# Power.net
KiCad netlist of a schematic drawn in Altium Designer
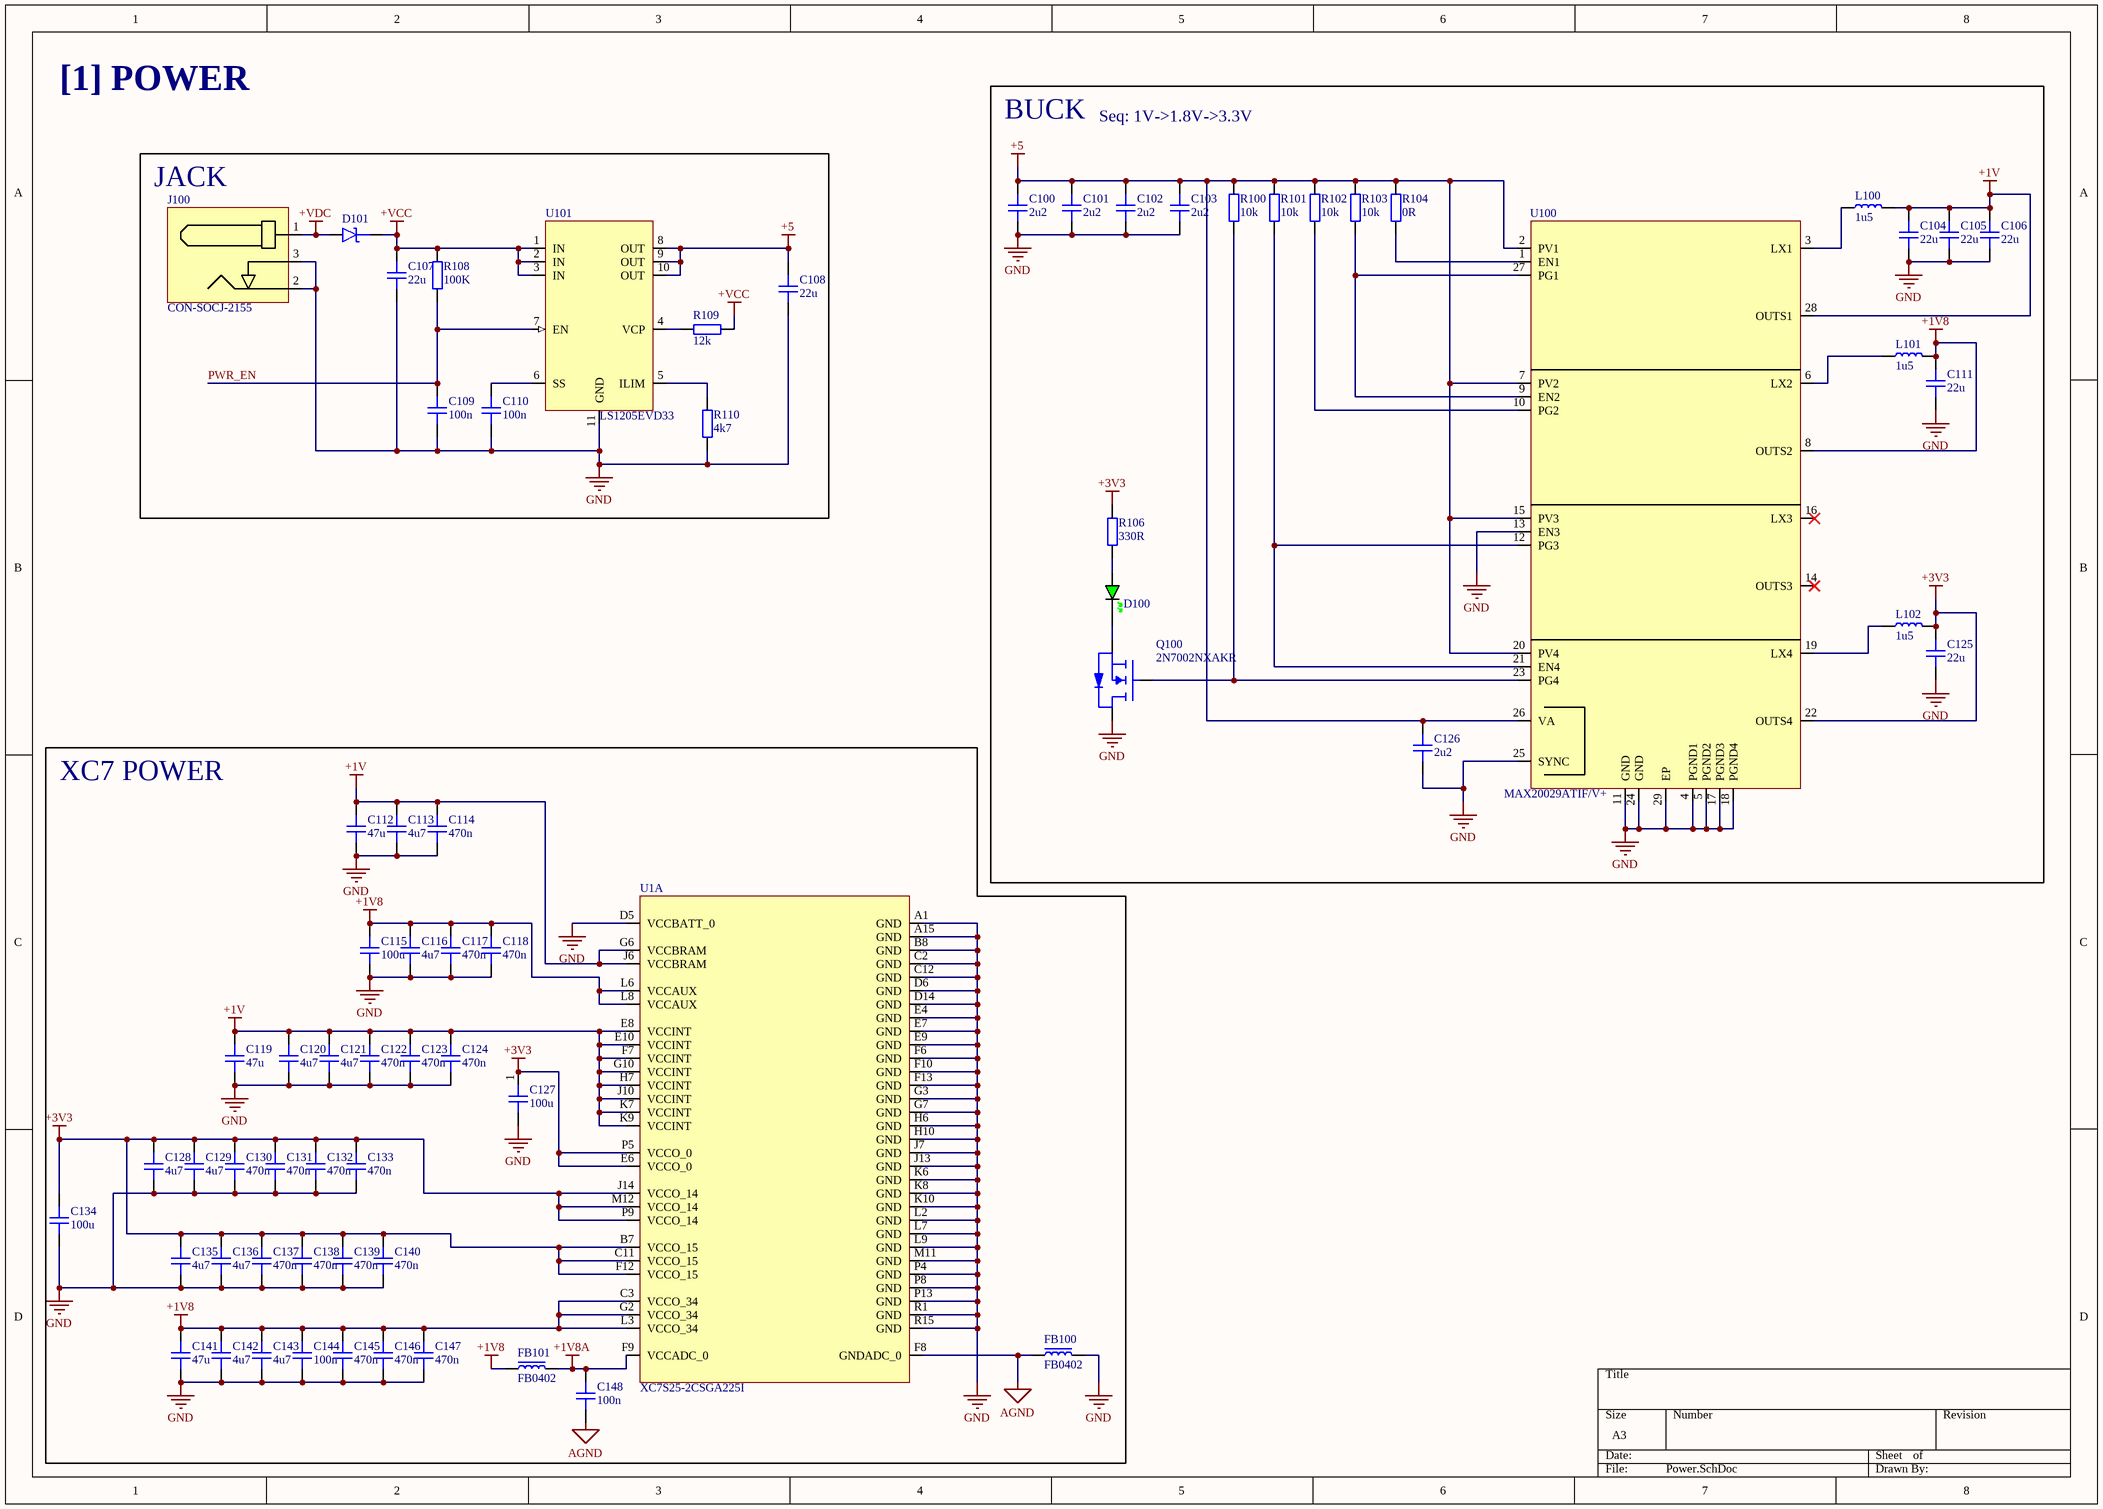
[diagram p0: Power.SchDoc]

(export (version "E")
  (design (tool "Eeschema 10.0.6"))
  (components
    (comp (ref "C100")
      (value "2u2")
      (footprint "CAP_0603")
      (description "Capacitor SMD 0603")
      (libsource (lib "Schematic-Lib-PhilsLab") (part "CAP_0603"))
    )
    (comp (ref "C101")
      (value "2u2")
      (footprint "CAP_0603")
      (description "Capacitor SMD 0603")
      (libsource (lib "Schematic-Lib-PhilsLab") (part "CAP_0603"))
    )
    (comp (ref "C102")
      (value "2u2")
      (footprint "CAP_0603")
      (description "Capacitor SMD 0603")
      (libsource (lib "Schematic-Lib-PhilsLab") (part "CAP_0603"))
    )
    (comp (ref "C103")
      (value "2u2")
      (footprint "CAP_0603")
      (description "Capacitor SMD 0603")
      (libsource (lib "Schematic-Lib-PhilsLab") (part "CAP_0603"))
    )
    (comp (ref "C104")
      (value "22u")
      (footprint "CAP_0402")
      (description "Capacitor SMD 0402")
      (libsource (lib "Schematic-Lib-PhilsLab") (part "CAP_0402"))
    )
    (comp (ref "C105")
      (value "22u")
      (footprint "CAP_0402")
      (description "Capacitor SMD 0402")
      (libsource (lib "Schematic-Lib-PhilsLab") (part "CAP_0402"))
    )
    (comp (ref "C106")
      (value "22u")
      (footprint "CAP_0402")
      (description "Capacitor SMD 0402")
      (libsource (lib "Schematic-Lib-PhilsLab") (part "CAP_0402"))
    )
    (comp (ref "C107")
      (value "22u")
      (footprint "CAP_0402")
      (description "Capacitor SMD 0402")
      (libsource (lib "Schematic-Lib-PhilsLab") (part "CAP_0402"))
    )
    (comp (ref "C108")
      (value "22u")
      (footprint "CAP_0402")
      (description "Capacitor SMD 0402")
      (libsource (lib "Schematic-Lib-PhilsLab") (part "CAP_0402"))
    )
    (comp (ref "C109")
      (value "100n")
      (footprint "CAP_0402")
      (description "Capacitor SMD 0402")
      (libsource (lib "Schematic-Lib-PhilsLab") (part "CAP_0402"))
    )
    (comp (ref "C110")
      (value "100n")
      (footprint "CAP_0402")
      (description "Capacitor SMD 0402")
      (libsource (lib "Schematic-Lib-PhilsLab") (part "CAP_0402"))
    )
    (comp (ref "C111")
      (value "22u")
      (footprint "CAP_0402")
      (description "Capacitor SMD 0402")
      (libsource (lib "Schematic-Lib-PhilsLab") (part "CAP_0402"))
    )
    (comp (ref "C112")
      (value "47u")
      (footprint "CAP_0805")
      (description "Capacitor SMD 0805")
      (libsource (lib "") (part "CAP_0805_1"))
    )
    (comp (ref "C113")
      (value "4u7")
      (footprint "CAP_0402")
      (description "Capacitor SMD 0402")
      (libsource (lib "Schematic-Lib-PhilsLab") (part "CAP_0402"))
    )
    (comp (ref "C114")
      (value "470n")
      (footprint "CAP_0201")
      (description "Capacitor SMD 0201")
      (libsource (lib "Schematic-Lib-PhilsLab") (part "CAP_0201"))
    )
    (comp (ref "C115")
      (value "100u")
      (footprint "CAP_0805")
      (description "Capacitor SMD 0805")
      (libsource (lib "") (part "CAP_0805_1"))
    )
    (comp (ref "C116")
      (value "4u7")
      (footprint "CAP_0402")
      (description "Capacitor SMD 0402")
      (libsource (lib "Schematic-Lib-PhilsLab") (part "CAP_0402"))
    )
    (comp (ref "C117")
      (value "470n")
      (footprint "CAP_0201")
      (description "Capacitor SMD 0201")
      (libsource (lib "Schematic-Lib-PhilsLab") (part "CAP_0201"))
    )
    (comp (ref "C118")
      (value "470n")
      (footprint "CAP_0201")
      (description "Capacitor SMD 0201")
      (libsource (lib "Schematic-Lib-PhilsLab") (part "CAP_0201"))
    )
    (comp (ref "C119")
      (value "47u")
      (footprint "CAP_0805")
      (description "Capacitor SMD 0805")
      (libsource (lib "") (part "CAP_0805_1"))
    )
    (comp (ref "C120")
      (value "4u7")
      (footprint "CAP_0402")
      (description "Capacitor SMD 0402")
      (libsource (lib "Schematic-Lib-PhilsLab") (part "CAP_0402"))
    )
    (comp (ref "C121")
      (value "4u7")
      (footprint "CAP_0402")
      (description "Capacitor SMD 0402")
      (libsource (lib "Schematic-Lib-PhilsLab") (part "CAP_0402"))
    )
    (comp (ref "C122")
      (value "470n")
      (footprint "CAP_0201")
      (description "Capacitor SMD 0201")
      (libsource (lib "Schematic-Lib-PhilsLab") (part "CAP_0201"))
    )
    (comp (ref "C123")
      (value "470n")
      (footprint "CAP_0201")
      (description "Capacitor SMD 0201")
      (libsource (lib "Schematic-Lib-PhilsLab") (part "CAP_0201"))
    )
    (comp (ref "C124")
      (value "470n")
      (footprint "CAP_0201")
      (description "Capacitor SMD 0201")
      (libsource (lib "Schematic-Lib-PhilsLab") (part "CAP_0201"))
    )
    (comp (ref "C125")
      (value "22u")
      (footprint "CAP_0402")
      (description "Capacitor SMD 0402")
      (libsource (lib "Schematic-Lib-PhilsLab") (part "CAP_0402"))
    )
    (comp (ref "C126")
      (value "2u2")
      (footprint "CAP_0603")
      (description "Capacitor SMD 0603")
      (libsource (lib "Schematic-Lib-PhilsLab") (part "CAP_0603"))
    )
    (comp (ref "C127")
      (value "100u")
      (footprint "CAP_0805")
      (description "Capacitor SMD 0805")
      (libsource (lib "Schematic-Lib-PhilsLab") (part "CAP_0805"))
    )
    (comp (ref "C128")
      (value "4u7")
      (footprint "CAP_0402")
      (description "Capacitor SMD 0402")
      (libsource (lib "Schematic-Lib-PhilsLab") (part "CAP_0402"))
    )
    (comp (ref "C129")
      (value "4u7")
      (footprint "CAP_0402")
      (description "Capacitor SMD 0402")
      (libsource (lib "Schematic-Lib-PhilsLab") (part "CAP_0402"))
    )
    (comp (ref "C130")
      (value "470n")
      (footprint "CAP_0201")
      (description "Capacitor SMD 0201")
      (libsource (lib "Schematic-Lib-PhilsLab") (part "CAP_0201"))
    )
    (comp (ref "C131")
      (value "470n")
      (footprint "CAP_0201")
      (description "Capacitor SMD 0201")
      (libsource (lib "Schematic-Lib-PhilsLab") (part "CAP_0201"))
    )
    (comp (ref "C132")
      (value "470n")
      (footprint "CAP_0201")
      (description "Capacitor SMD 0201")
      (libsource (lib "Schematic-Lib-PhilsLab") (part "CAP_0201"))
    )
    (comp (ref "C133")
      (value "470n")
      (footprint "CAP_0201")
      (description "Capacitor SMD 0201")
      (libsource (lib "Schematic-Lib-PhilsLab") (part "CAP_0201"))
    )
    (comp (ref "C134")
      (value "100u")
      (footprint "CAP_0805")
      (description "Capacitor SMD 0805")
      (libsource (lib "") (part "CAP_0805_1"))
    )
    (comp (ref "C135")
      (value "4u7")
      (footprint "CAP_0402")
      (description "Capacitor SMD 0402")
      (libsource (lib "Schematic-Lib-PhilsLab") (part "CAP_0402"))
    )
    (comp (ref "C136")
      (value "4u7")
      (footprint "CAP_0402")
      (description "Capacitor SMD 0402")
      (libsource (lib "Schematic-Lib-PhilsLab") (part "CAP_0402"))
    )
    (comp (ref "C137")
      (value "470n")
      (footprint "CAP_0201")
      (description "Capacitor SMD 0201")
      (libsource (lib "Schematic-Lib-PhilsLab") (part "CAP_0201"))
    )
    (comp (ref "C138")
      (value "470n")
      (footprint "CAP_0201")
      (description "Capacitor SMD 0201")
      (libsource (lib "Schematic-Lib-PhilsLab") (part "CAP_0201"))
    )
    (comp (ref "C139")
      (value "470n")
      (footprint "CAP_0201")
      (description "Capacitor SMD 0201")
      (libsource (lib "Schematic-Lib-PhilsLab") (part "CAP_0201"))
    )
    (comp (ref "C140")
      (value "470n")
      (footprint "CAP_0201")
      (description "Capacitor SMD 0201")
      (libsource (lib "Schematic-Lib-PhilsLab") (part "CAP_0201"))
    )
    (comp (ref "C141")
      (value "47u")
      (footprint "CAP_0805")
      (description "Capacitor SMD 0805")
      (libsource (lib "") (part "CAP_0805_1"))
    )
    (comp (ref "C142")
      (value "4u7")
      (footprint "CAP_0402")
      (description "Capacitor SMD 0402")
      (libsource (lib "Schematic-Lib-PhilsLab") (part "CAP_0402"))
    )
    (comp (ref "C143")
      (value "4u7")
      (footprint "CAP_0402")
      (description "Capacitor SMD 0402")
      (libsource (lib "Schematic-Lib-PhilsLab") (part "CAP_0402"))
    )
    (comp (ref "C144")
      (value "100n")
      (footprint "CAP_0201")
      (description "Capacitor SMD 0201")
      (libsource (lib "Schematic-Lib-PhilsLab") (part "CAP_0201"))
    )
    (comp (ref "C145")
      (value "470n")
      (footprint "CAP_0201")
      (description "Capacitor SMD 0201")
      (libsource (lib "Schematic-Lib-PhilsLab") (part "CAP_0201"))
    )
    (comp (ref "C146")
      (value "470n")
      (footprint "CAP_0201")
      (description "Capacitor SMD 0201")
      (libsource (lib "Schematic-Lib-PhilsLab") (part "CAP_0201"))
    )
    (comp (ref "C147")
      (value "470n")
      (footprint "CAP_0201")
      (description "Capacitor SMD 0201")
      (libsource (lib "Schematic-Lib-PhilsLab") (part "CAP_0201"))
    )
    (comp (ref "C148")
      (value "100n")
      (footprint "CAP_0201")
      (description "Capacitor SMD 0201")
      (libsource (lib "Schematic-Lib-PhilsLab") (part "CAP_0201"))
    )
    (comp (ref "D100")
      (value "GREEN")
      (footprint "LED_0402_GREEN")
      (description "LED 0402 GREEN SMD")
      (libsource (lib "Schematic-Lib-PhilsLab") (part "LED_0402_GREEN"))
    )
    (comp (ref "D101")
      (value "D_SCHOTTKY_SMC")
      (footprint "SMC-DO-214AB")
      (description "Diode Schottky SMD SMC (DO-214AB)")
      (libsource (lib "Schematic-Lib-PhilsLab") (part "D_SCHOTTKY_SMC"))
    )
    (comp (ref "FB100")
      (value "FB0402")
      (footprint "FB_0402")
      (description "Ferrite Bead SMD 0402")
      (libsource (lib "Schematic-Lib-PhilsLab") (part "FB_0402"))
    )
    (comp (ref "FB101")
      (value "FB0402")
      (footprint "FB_0402")
      (description "Ferrite Bead SMD 0402")
      (libsource (lib "Schematic-Lib-PhilsLab") (part "FB_0402"))
    )
    (comp (ref "J100")
      (value "CON-SOCJ-2155")
      (footprint "CON-SOCJ-2155")
      (description "DC Barrell Jack 2.1mm 30V 2.5A THT")
      (fields (field (name "MANUFACTURER") "Gravitech"))
      (libsource (lib "Schematic-Lib-PhilsLab") (part "CON-SOCJ-2155"))
    )
    (comp (ref "L100")
      (value "1u5")
      (footprint "MWSA0603S")
      (description "Power Inductor SMD Sunlord MWSA0603S")
      (fields (field (name "MANUFACTURER") "Sunlord") (field (name "MANUFACTURER PART NUMBER") "MWSA0603S-"))
      (libsource (lib "Schematic-Lib-PhilsLab") (part "MWSA0603S"))
    )
    (comp (ref "L101")
      (value "1u5")
      (footprint "MWSA0603S")
      (description "Power Inductor SMD Sunlord MWSA0603S")
      (fields (field (name "MANUFACTURER") "Sunlord") (field (name "MANUFACTURER PART NUMBER") "MWSA0603S-"))
      (libsource (lib "Schematic-Lib-PhilsLab") (part "MWSA0603S"))
    )
    (comp (ref "L102")
      (value "1u5")
      (footprint "MWSA0603S")
      (description "Power Inductor SMD Sunlord MWSA0603S")
      (fields (field (name "MANUFACTURER") "Sunlord") (field (name "MANUFACTURER PART NUMBER") "MWSA0603S-"))
      (libsource (lib "Schematic-Lib-PhilsLab") (part "MWSA0603S"))
    )
    (comp (ref "Q100")
      (value "2N7002NXAKR")
      (footprint "SSM3J338R,LF-SOT23-F")
      (description "MOSFET N-Channel Vds=60V Id=300mA with ESD Protection")
      (fields (field (name "MANUFACTURER") "Nexperia"))
      (libsource (lib "Schematic-Lib-PhilsLab") (part "2N7002NXAKR"))
    )
    (comp (ref "R100")
      (value "10k")
      (footprint "RES_0402")
      (description "Resistor SMD 0402")
      (libsource (lib "Schematic-Lib-PhilsLab") (part "RES_0402"))
    )
    (comp (ref "R101")
      (value "10k")
      (footprint "RES_0402")
      (description "Resistor SMD 0402")
      (libsource (lib "Schematic-Lib-PhilsLab") (part "RES_0402"))
    )
    (comp (ref "R102")
      (value "10k")
      (footprint "RES_0402")
      (description "Resistor SMD 0402")
      (libsource (lib "Schematic-Lib-PhilsLab") (part "RES_0402"))
    )
    (comp (ref "R103")
      (value "10k")
      (footprint "RES_0402")
      (description "Resistor SMD 0402")
      (libsource (lib "Schematic-Lib-PhilsLab") (part "RES_0402"))
    )
    (comp (ref "R104")
      (value "0R")
      (footprint "RES_0402")
      (description "Resistor SMD 0402")
      (libsource (lib "Schematic-Lib-PhilsLab") (part "RES_0402"))
    )
    (comp (ref "R106")
      (value "330R")
      (footprint "RES_0402")
      (description "Resistor SMD 0402")
      (libsource (lib "Schematic-Lib-PhilsLab") (part "RES_0402"))
    )
    (comp (ref "R108")
      (value "100K")
      (footprint "RES_0603")
      (description "Resistor SMD 0603")
      (libsource (lib "Schematic-Lib-PhilsLab") (part "RES_0603"))
    )
    (comp (ref "R109")
      (value "12k")
      (footprint "RES_0402")
      (description "Resistor SMD 0402")
      (libsource (lib "Schematic-Lib-PhilsLab") (part "RES_0402"))
    )
    (comp (ref "R110")
      (value "4k7")
      (footprint "RES_0402")
      (description "Resistor SMD 0402")
      (libsource (lib "Schematic-Lib-PhilsLab") (part "RES_0402"))
    )
    (comp (ref "U1")
      (value "XC7S25-2CSGA225I")
      (footprint "CSGA225")
      (fields (field (name "MANUFACTURER") "Xilinx"))
      (libsource (lib "Schematic-Lib-PhilsLab") (part "XC7S25-2CSGA225I"))
    )
    (comp (ref "U100")
      (value "MAX20029ATIF/V+")
      (footprint "TQFN-28-5x5-EP")
      (description "Switching Voltage Regulator Buck 4-Channel 700mV to 4V 1.5A TQFN-EP-28")
      (fields (field (name "MANUFACTURER") "Maxim Integrated"))
      (libsource (lib "Schematic-Lib-PhilsLab") (part "MAX20029ATIF/V+"))
    )
    (comp (ref "U101")
      (value "LS1205EVD33")
      (footprint "DFN3x3_10L")
      (description "18V, 5A eFuse with Programmable Current Limit and Output Voltage Clamp")
      (fields (field (name "MANUFACTURER") "Littelfuse"))
      (libsource (lib "Schematic-Lib-PhilsLab") (part "LS1205EVD33"))
    )
  )
  (nets
    (net (code "1") (name "+1V") (class "Default")
      (node (ref "C104") (pin "2") (pinfunction "2_2") (pintype "passive"))
      (node (ref "C105") (pin "2") (pinfunction "2_2") (pintype "passive"))
      (node (ref "C106") (pin "2") (pinfunction "2_2") (pintype "passive"))
      (node (ref "C112") (pin "2") (pinfunction "2_2") (pintype "passive"))
      (node (ref "C113") (pin "2") (pinfunction "2_2") (pintype "passive"))
      (node (ref "C114") (pin "2") (pinfunction "2_2") (pintype "passive"))
      (node (ref "C119") (pin "2") (pinfunction "2_2") (pintype "passive"))
      (node (ref "C120") (pin "2") (pinfunction "2_2") (pintype "passive"))
      (node (ref "C121") (pin "2") (pinfunction "2_2") (pintype "passive"))
      (node (ref "C122") (pin "2") (pinfunction "2_2") (pintype "passive"))
      (node (ref "C123") (pin "2") (pinfunction "2_2") (pintype "passive"))
      (node (ref "C124") (pin "2") (pinfunction "2_2") (pintype "passive"))
      (node (ref "L100") (pin "2") (pinfunction "2_2") (pintype "passive"))
      (node (ref "U1") (pin "E10") (pinfunction "VCCINT_E10") (pintype "power_in"))
      (node (ref "U1") (pin "E8") (pinfunction "VCCINT_E8") (pintype "power_in"))
      (node (ref "U1") (pin "F7") (pinfunction "VCCINT_F7") (pintype "power_in"))
      (node (ref "U1") (pin "G10") (pinfunction "VCCINT_G10") (pintype "power_in"))
      (node (ref "U1") (pin "G6") (pinfunction "VCCBRAM_G6") (pintype "power_in"))
      (node (ref "U1") (pin "H7") (pinfunction "VCCINT_H7") (pintype "power_in"))
      (node (ref "U1") (pin "J10") (pinfunction "VCCINT_J10") (pintype "power_in"))
      (node (ref "U1") (pin "J6") (pinfunction "VCCBRAM_J6") (pintype "power_in"))
      (node (ref "U1") (pin "K7") (pinfunction "VCCINT_K7") (pintype "power_in"))
      (node (ref "U1") (pin "K9") (pinfunction "VCCINT_K9") (pintype "power_in"))
      (node (ref "U100") (pin "28") (pinfunction "OUTS1_28") (pintype "passive"))
    )
    (net (code "2") (name "+1V8") (class "Default")
      (node (ref "C111") (pin "2") (pinfunction "2_2") (pintype "passive"))
      (node (ref "C115") (pin "2") (pinfunction "2_2") (pintype "passive"))
      (node (ref "C116") (pin "2") (pinfunction "2_2") (pintype "passive"))
      (node (ref "C117") (pin "2") (pinfunction "2_2") (pintype "passive"))
      (node (ref "C118") (pin "2") (pinfunction "2_2") (pintype "passive"))
      (node (ref "C141") (pin "2") (pinfunction "2_2") (pintype "passive"))
      (node (ref "C142") (pin "2") (pinfunction "2_2") (pintype "passive"))
      (node (ref "C143") (pin "2") (pinfunction "2_2") (pintype "passive"))
      (node (ref "C144") (pin "2") (pinfunction "2_2") (pintype "passive"))
      (node (ref "C145") (pin "2") (pinfunction "2_2") (pintype "passive"))
      (node (ref "C146") (pin "2") (pinfunction "2_2") (pintype "passive"))
      (node (ref "C147") (pin "2") (pinfunction "2_2") (pintype "passive"))
      (node (ref "FB101") (pin "1") (pinfunction "1_1") (pintype "passive"))
      (node (ref "L101") (pin "2") (pinfunction "2_2") (pintype "passive"))
      (node (ref "U1") (pin "C3") (pinfunction "VCCO_34_C3") (pintype "power_in"))
      (node (ref "U1") (pin "G2") (pinfunction "VCCO_34_G2") (pintype "power_in"))
      (node (ref "U1") (pin "L3") (pinfunction "VCCO_34_L3") (pintype "power_in"))
      (node (ref "U1") (pin "L6") (pinfunction "VCCAUX_L6") (pintype "power_in"))
      (node (ref "U1") (pin "L8") (pinfunction "VCCAUX_L8") (pintype "power_in"))
      (node (ref "U100") (pin "8") (pinfunction "OUTS2_8") (pintype "passive"))
    )
    (net (code "3") (name "+1V8A") (class "Default")
      (node (ref "C148") (pin "2") (pinfunction "2_2") (pintype "passive"))
      (node (ref "FB101") (pin "2") (pinfunction "2_2") (pintype "passive"))
      (node (ref "U1") (pin "F9") (pinfunction "VCCADC_0_F9") (pintype "power_in"))
    )
    (net (code "4") (name "+3V3") (class "Default")
      (node (ref "C125") (pin "2") (pinfunction "2_2") (pintype "passive"))
      (node (ref "C127") (pin "1") (pinfunction "1_1") (pintype "passive"))
      (node (ref "C128") (pin "2") (pinfunction "2_2") (pintype "passive"))
      (node (ref "C129") (pin "2") (pinfunction "2_2") (pintype "passive"))
      (node (ref "C130") (pin "2") (pinfunction "2_2") (pintype "passive"))
      (node (ref "C131") (pin "2") (pinfunction "2_2") (pintype "passive"))
      (node (ref "C132") (pin "2") (pinfunction "2_2") (pintype "passive"))
      (node (ref "C133") (pin "2") (pinfunction "2_2") (pintype "passive"))
      (node (ref "C134") (pin "2") (pinfunction "2_2") (pintype "passive"))
      (node (ref "C135") (pin "2") (pinfunction "2_2") (pintype "passive"))
      (node (ref "C136") (pin "2") (pinfunction "2_2") (pintype "passive"))
      (node (ref "C137") (pin "2") (pinfunction "2_2") (pintype "passive"))
      (node (ref "C138") (pin "2") (pinfunction "2_2") (pintype "passive"))
      (node (ref "C139") (pin "2") (pinfunction "2_2") (pintype "passive"))
      (node (ref "C140") (pin "2") (pinfunction "2_2") (pintype "passive"))
      (node (ref "L102") (pin "2") (pinfunction "2_2") (pintype "passive"))
      (node (ref "R106") (pin "2") (pinfunction "2_2") (pintype "passive"))
      (node (ref "U1") (pin "B7") (pinfunction "VCCO_15_B7") (pintype "power_in"))
      (node (ref "U1") (pin "C11") (pinfunction "VCCO_15_C11") (pintype "power_in"))
      (node (ref "U1") (pin "E6") (pinfunction "VCCO_0_E6") (pintype "power_in"))
      (node (ref "U1") (pin "F12") (pinfunction "VCCO_15_F12") (pintype "power_in"))
      (node (ref "U1") (pin "J14") (pinfunction "VCCO_14_J14") (pintype "power_in"))
      (node (ref "U1") (pin "M12") (pinfunction "VCCO_14_M12") (pintype "power_in"))
      (node (ref "U1") (pin "P5") (pinfunction "VCCO_0_P5") (pintype "power_in"))
      (node (ref "U1") (pin "P9") (pinfunction "VCCO_14_P9") (pintype "power_in"))
      (node (ref "U100") (pin "22") (pinfunction "OUTS4_22") (pintype "passive"))
    )
    (net (code "5") (name "+5") (class "Default")
      (node (ref "C100") (pin "2") (pinfunction "2_2") (pintype "passive"))
      (node (ref "C101") (pin "2") (pinfunction "2_2") (pintype "passive"))
      (node (ref "C102") (pin "2") (pinfunction "2_2") (pintype "passive"))
      (node (ref "C103") (pin "2") (pinfunction "2_2") (pintype "passive"))
      (node (ref "C108") (pin "2") (pinfunction "2_2") (pintype "passive"))
      (node (ref "C126") (pin "2") (pinfunction "2_2") (pintype "passive"))
      (node (ref "R100") (pin "2") (pinfunction "2_2") (pintype "passive"))
      (node (ref "R101") (pin "2") (pinfunction "2_2") (pintype "passive"))
      (node (ref "R102") (pin "2") (pinfunction "2_2") (pintype "passive"))
      (node (ref "R103") (pin "2") (pinfunction "2_2") (pintype "passive"))
      (node (ref "R104") (pin "2") (pinfunction "2_2") (pintype "passive"))
      (node (ref "U100") (pin "15") (pinfunction "PV3_15") (pintype "passive"))
      (node (ref "U100") (pin "2") (pinfunction "PV1_2") (pintype "passive"))
      (node (ref "U100") (pin "20") (pinfunction "PV4_20") (pintype "passive"))
      (node (ref "U100") (pin "26") (pinfunction "VA_26") (pintype "passive"))
      (node (ref "U100") (pin "7") (pinfunction "PV2_7") (pintype "passive"))
      (node (ref "U101") (pin "10") (pinfunction "OUT_10") (pintype "power_in"))
      (node (ref "U101") (pin "8") (pinfunction "OUT_8") (pintype "power_in"))
      (node (ref "U101") (pin "9") (pinfunction "OUT_9") (pintype "power_in"))
    )
    (net (code "6") (name "+VCC") (class "Default")
      (node (ref "C107") (pin "2") (pinfunction "2_2") (pintype "passive"))
      (node (ref "D101") (pin "K") (pinfunction "K_K") (pintype "passive"))
      (node (ref "R108") (pin "2") (pinfunction "2_2") (pintype "passive"))
      (node (ref "R109") (pin "1") (pinfunction "1_1") (pintype "passive"))
      (node (ref "U101") (pin "1") (pinfunction "IN_1") (pintype "power_in"))
      (node (ref "U101") (pin "2") (pinfunction "IN_2") (pintype "power_in"))
      (node (ref "U101") (pin "3") (pinfunction "IN_3") (pintype "power_in"))
    )
    (net (code "7") (name "+VDC") (class "Default")
      (node (ref "D101") (pin "A") (pinfunction "A_A") (pintype "passive"))
      (node (ref "J100") (pin "1") (pinfunction "1_1") (pintype "passive"))
    )
    (net (code "8") (name "/PWR_EN") (class "Default")
      (node (ref "C109") (pin "2") (pinfunction "2_2") (pintype "passive"))
      (node (ref "R108") (pin "1") (pinfunction "1_1") (pintype "passive"))
      (node (ref "U101") (pin "7") (pinfunction "EN_7") (pintype "input"))
    )
    (net (code "9") (name "AGND") (class "Default")
      (node (ref "C148") (pin "1") (pinfunction "1_1") (pintype "passive"))
      (node (ref "FB100") (pin "1") (pinfunction "1_1") (pintype "passive"))
      (node (ref "U1") (pin "F8") (pinfunction "GNDADC_0_F8") (pintype "power_in"))
    )
    (net (code "10") (name "GND") (class "Default")
      (node (ref "C100") (pin "1") (pinfunction "1_1") (pintype "passive"))
      (node (ref "C101") (pin "1") (pinfunction "1_1") (pintype "passive"))
      (node (ref "C102") (pin "1") (pinfunction "1_1") (pintype "passive"))
      (node (ref "C103") (pin "1") (pinfunction "1_1") (pintype "passive"))
      (node (ref "C104") (pin "1") (pinfunction "1_1") (pintype "passive"))
      (node (ref "C105") (pin "1") (pinfunction "1_1") (pintype "passive"))
      (node (ref "C106") (pin "1") (pinfunction "1_1") (pintype "passive"))
      (node (ref "C107") (pin "1") (pinfunction "1_1") (pintype "passive"))
      (node (ref "C108") (pin "1") (pinfunction "1_1") (pintype "passive"))
      (node (ref "C109") (pin "1") (pinfunction "1_1") (pintype "passive"))
      (node (ref "C110") (pin "1") (pinfunction "1_1") (pintype "passive"))
      (node (ref "C111") (pin "1") (pinfunction "1_1") (pintype "passive"))
      (node (ref "C112") (pin "1") (pinfunction "1_1") (pintype "passive"))
      (node (ref "C113") (pin "1") (pinfunction "1_1") (pintype "passive"))
      (node (ref "C114") (pin "1") (pinfunction "1_1") (pintype "passive"))
      (node (ref "C115") (pin "1") (pinfunction "1_1") (pintype "passive"))
      (node (ref "C116") (pin "1") (pinfunction "1_1") (pintype "passive"))
      (node (ref "C117") (pin "1") (pinfunction "1_1") (pintype "passive"))
      (node (ref "C118") (pin "1") (pinfunction "1_1") (pintype "passive"))
      (node (ref "C119") (pin "1") (pinfunction "1_1") (pintype "passive"))
      (node (ref "C120") (pin "1") (pinfunction "1_1") (pintype "passive"))
      (node (ref "C121") (pin "1") (pinfunction "1_1") (pintype "passive"))
      (node (ref "C122") (pin "1") (pinfunction "1_1") (pintype "passive"))
      (node (ref "C123") (pin "1") (pinfunction "1_1") (pintype "passive"))
      (node (ref "C124") (pin "1") (pinfunction "1_1") (pintype "passive"))
      (node (ref "C125") (pin "1") (pinfunction "1_1") (pintype "passive"))
      (node (ref "C126") (pin "1") (pinfunction "1_1") (pintype "passive"))
      (node (ref "C127") (pin "2") (pinfunction "2_2") (pintype "passive"))
      (node (ref "C128") (pin "1") (pinfunction "1_1") (pintype "passive"))
      (node (ref "C129") (pin "1") (pinfunction "1_1") (pintype "passive"))
      (node (ref "C130") (pin "1") (pinfunction "1_1") (pintype "passive"))
      (node (ref "C131") (pin "1") (pinfunction "1_1") (pintype "passive"))
      (node (ref "C132") (pin "1") (pinfunction "1_1") (pintype "passive"))
      (node (ref "C133") (pin "1") (pinfunction "1_1") (pintype "passive"))
      (node (ref "C134") (pin "1") (pinfunction "1_1") (pintype "passive"))
      (node (ref "C135") (pin "1") (pinfunction "1_1") (pintype "passive"))
      (node (ref "C136") (pin "1") (pinfunction "1_1") (pintype "passive"))
      (node (ref "C137") (pin "1") (pinfunction "1_1") (pintype "passive"))
      (node (ref "C138") (pin "1") (pinfunction "1_1") (pintype "passive"))
      (node (ref "C139") (pin "1") (pinfunction "1_1") (pintype "passive"))
      (node (ref "C140") (pin "1") (pinfunction "1_1") (pintype "passive"))
      (node (ref "C141") (pin "1") (pinfunction "1_1") (pintype "passive"))
      (node (ref "C142") (pin "1") (pinfunction "1_1") (pintype "passive"))
      (node (ref "C143") (pin "1") (pinfunction "1_1") (pintype "passive"))
      (node (ref "C144") (pin "1") (pinfunction "1_1") (pintype "passive"))
      (node (ref "C145") (pin "1") (pinfunction "1_1") (pintype "passive"))
      (node (ref "C146") (pin "1") (pinfunction "1_1") (pintype "passive"))
      (node (ref "C147") (pin "1") (pinfunction "1_1") (pintype "passive"))
      (node (ref "FB100") (pin "2") (pinfunction "2_2") (pintype "passive"))
      (node (ref "J100") (pin "2") (pinfunction "2_2") (pintype "passive"))
      (node (ref "J100") (pin "3") (pinfunction "3_3") (pintype "passive"))
      (node (ref "Q100") (pin "D") (pinfunction "D_D") (pintype "passive"))
      (node (ref "R110") (pin "1") (pinfunction "1_1") (pintype "passive"))
      (node (ref "U1") (pin "A1") (pinfunction "GND_A1") (pintype "power_in"))
      (node (ref "U1") (pin "A15") (pinfunction "GND_A15") (pintype "power_in"))
      (node (ref "U1") (pin "B8") (pinfunction "GND_B8") (pintype "power_in"))
      (node (ref "U1") (pin "C12") (pinfunction "GND_C12") (pintype "power_in"))
      (node (ref "U1") (pin "C2") (pinfunction "GND_C2") (pintype "power_in"))
      (node (ref "U1") (pin "D14") (pinfunction "GND_D14") (pintype "power_in"))
      (node (ref "U1") (pin "D5") (pinfunction "VCCBATT_0_D5") (pintype "power_in"))
      (node (ref "U1") (pin "D6") (pinfunction "GND_D6") (pintype "power_in"))
      (node (ref "U1") (pin "E4") (pinfunction "GND_E4") (pintype "power_in"))
      (node (ref "U1") (pin "E7") (pinfunction "GND_E7") (pintype "power_in"))
      (node (ref "U1") (pin "E9") (pinfunction "GND_E9") (pintype "power_in"))
      (node (ref "U1") (pin "F10") (pinfunction "GND_F10") (pintype "power_in"))
      (node (ref "U1") (pin "F13") (pinfunction "GND_F13") (pintype "power_in"))
      (node (ref "U1") (pin "F6") (pinfunction "GND_F6") (pintype "power_in"))
      (node (ref "U1") (pin "G3") (pinfunction "GND_G3") (pintype "power_in"))
      (node (ref "U1") (pin "G7") (pinfunction "GND_G7") (pintype "power_in"))
      (node (ref "U1") (pin "H10") (pinfunction "GND_H10") (pintype "power_in"))
      (node (ref "U1") (pin "H6") (pinfunction "GND_H6") (pintype "power_in"))
      (node (ref "U1") (pin "J13") (pinfunction "GND_J13") (pintype "power_in"))
      (node (ref "U1") (pin "J7") (pinfunction "GND_J7") (pintype "power_in"))
      (node (ref "U1") (pin "K10") (pinfunction "GND_K10") (pintype "power_in"))
      (node (ref "U1") (pin "K6") (pinfunction "GND_K6") (pintype "power_in"))
      (node (ref "U1") (pin "K8") (pinfunction "GND_K8") (pintype "power_in"))
      (node (ref "U1") (pin "L2") (pinfunction "GND_L2") (pintype "power_in"))
      (node (ref "U1") (pin "L7") (pinfunction "GND_L7") (pintype "power_in"))
      (node (ref "U1") (pin "L9") (pinfunction "GND_L9") (pintype "power_in"))
      (node (ref "U1") (pin "M11") (pinfunction "GND_M11") (pintype "power_in"))
      (node (ref "U1") (pin "P13") (pinfunction "GND_P13") (pintype "power_in"))
      (node (ref "U1") (pin "P4") (pinfunction "GND_P4") (pintype "power_in"))
      (node (ref "U1") (pin "P8") (pinfunction "GND_P8") (pintype "power_in"))
      (node (ref "U1") (pin "R1") (pinfunction "GND_R1") (pintype "power_in"))
      (node (ref "U1") (pin "R15") (pinfunction "GND_R15") (pintype "power_in"))
      (node (ref "U100") (pin "11") (pinfunction "GND_11") (pintype "passive"))
      (node (ref "U100") (pin "13") (pinfunction "EN3_13") (pintype "passive"))
      (node (ref "U100") (pin "17") (pinfunction "PGND3_17") (pintype "passive"))
      (node (ref "U100") (pin "18") (pinfunction "PGND4_18") (pintype "passive"))
      (node (ref "U100") (pin "24") (pinfunction "GND_24") (pintype "passive"))
      (node (ref "U100") (pin "25") (pinfunction "SYNC_25") (pintype "passive"))
      (node (ref "U100") (pin "29") (pinfunction "EP_29") (pintype "passive"))
      (node (ref "U100") (pin "4") (pinfunction "PGND1_4") (pintype "passive"))
      (node (ref "U100") (pin "5") (pinfunction "PGND2_5") (pintype "passive"))
      (node (ref "U101") (pin "11") (pinfunction "GND_11") (pintype "power_in"))
    )
    (net (code "11") (name "Net-(D100-PadA)") (class "Default")
      (node (ref "D100") (pin "A") (pinfunction "A_A") (pintype "passive"))
      (node (ref "R106") (pin "1") (pinfunction "1_1") (pintype "passive"))
    )
    (net (code "12") (name "Net-(D100-PadK)") (class "Default")
      (node (ref "D100") (pin "K") (pinfunction "K_K") (pintype "passive"))
      (node (ref "Q100") (pin "S") (pinfunction "S_S") (pintype "passive"))
    )
    (net (code "13") (name "Net-(U100-EN1)") (class "Default")
      (node (ref "R104") (pin "1") (pinfunction "1_1") (pintype "passive"))
      (node (ref "U100") (pin "1") (pinfunction "EN1_1") (pintype "passive"))
    )
    (net (code "14") (name "Net-(U100-EN2)") (class "Default")
      (node (ref "R103") (pin "1") (pinfunction "1_1") (pintype "passive"))
      (node (ref "U100") (pin "27") (pinfunction "PG1_27") (pintype "passive"))
      (node (ref "U100") (pin "9") (pinfunction "EN2_9") (pintype "passive"))
    )
    (net (code "15") (name "Net-(U100-EN4)") (class "Default")
      (node (ref "R101") (pin "1") (pinfunction "1_1") (pintype "passive"))
      (node (ref "U100") (pin "12") (pinfunction "PG3_12") (pintype "passive"))
      (node (ref "U100") (pin "21") (pinfunction "EN4_21") (pintype "passive"))
    )
    (net (code "16") (name "Net-(U100-LX1)") (class "Default")
      (node (ref "L100") (pin "1") (pinfunction "1_1") (pintype "passive"))
      (node (ref "U100") (pin "3") (pinfunction "LX1_3") (pintype "passive"))
    )
    (net (code "17") (name "Net-(U100-LX2)") (class "Default")
      (node (ref "L101") (pin "1") (pinfunction "1_1") (pintype "passive"))
      (node (ref "U100") (pin "6") (pinfunction "LX2_6") (pintype "passive"))
    )
    (net (code "18") (name "Net-(U100-LX4)") (class "Default")
      (node (ref "L102") (pin "1") (pinfunction "1_1") (pintype "passive"))
      (node (ref "U100") (pin "19") (pinfunction "LX4_19") (pintype "passive"))
    )
    (net (code "19") (name "Net-(U100-PG2)") (class "Default")
      (node (ref "R102") (pin "1") (pinfunction "1_1") (pintype "passive"))
      (node (ref "U100") (pin "10") (pinfunction "PG2_10") (pintype "passive"))
    )
    (net (code "20") (name "Net-(U100-PG4)") (class "Default")
      (node (ref "Q100") (pin "G") (pinfunction "G_G") (pintype "passive"))
      (node (ref "R100") (pin "1") (pinfunction "1_1") (pintype "passive"))
      (node (ref "U100") (pin "23") (pinfunction "PG4_23") (pintype "passive"))
    )
    (net (code "21") (name "Net-(U101-ILIM)") (class "Default")
      (node (ref "R110") (pin "2") (pinfunction "2_2") (pintype "passive"))
      (node (ref "U101") (pin "5") (pinfunction "ILIM_5") (pintype "passive"))
    )
    (net (code "22") (name "Net-(U101-SS)") (class "Default")
      (node (ref "C110") (pin "2") (pinfunction "2_2") (pintype "passive"))
      (node (ref "U101") (pin "6") (pinfunction "SS_6") (pintype "passive"))
    )
    (net (code "23") (name "Net-(U101-VCP)") (class "Default")
      (node (ref "R109") (pin "2") (pinfunction "2_2") (pintype "passive"))
      (node (ref "U101") (pin "4") (pinfunction "VCP_4") (pintype "passive"))
    )
    (net (code "24") (name "unconnected-(U100-LX3-Pad16)") (class "Default")
      (node (ref "U100") (pin "16") (pinfunction "LX3_16") (pintype "passive+no_connect"))
    )
    (net (code "25") (name "unconnected-(U100-OUTS3-Pad14)") (class "Default")
      (node (ref "U100") (pin "14") (pinfunction "OUTS3_14") (pintype "passive+no_connect"))
    )
  )
)
